# ESP32-Hutschiene-2_0.net
KiCad netlist of a schematic drawn in EAGLE
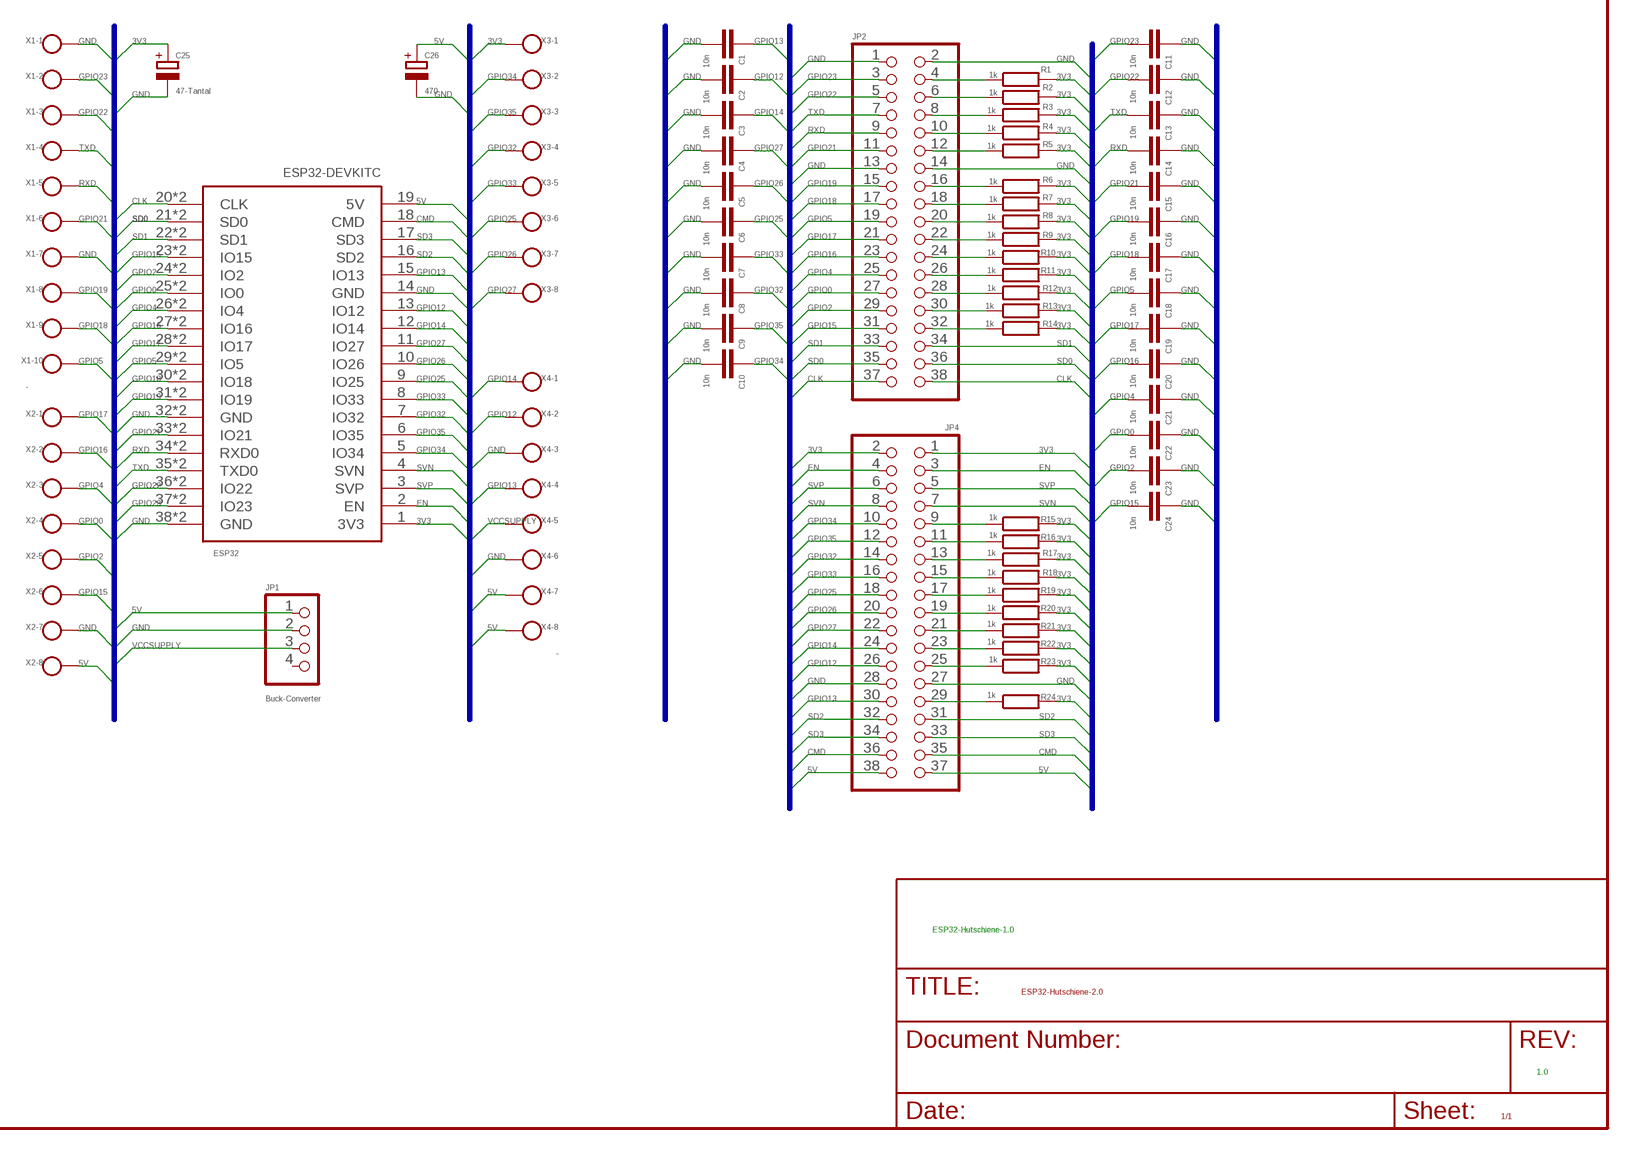
[diagram p0: schematic, sheet 1]

(export (version "E")
  (design (tool "Eeschema 10.0.6"))
  (components
    (comp (ref "C1")
      (value "10n")
      (footprint "eagle-import:C0603")
      (libsource (lib "eagle-import") (part "C-EUC0603"))
    )
    (comp (ref "C2")
      (value "10n")
      (footprint "eagle-import:C0603")
      (libsource (lib "eagle-import") (part "C-EUC0603"))
    )
    (comp (ref "C3")
      (value "10n")
      (footprint "eagle-import:C0603")
      (libsource (lib "eagle-import") (part "C-EUC0603"))
    )
    (comp (ref "C4")
      (value "10n")
      (footprint "eagle-import:C0603")
      (libsource (lib "eagle-import") (part "C-EUC0603"))
    )
    (comp (ref "C5")
      (value "10n")
      (footprint "eagle-import:C0603")
      (libsource (lib "eagle-import") (part "C-EUC0603"))
    )
    (comp (ref "C6")
      (value "10n")
      (footprint "eagle-import:C0603")
      (libsource (lib "eagle-import") (part "C-EUC0603"))
    )
    (comp (ref "C7")
      (value "10n")
      (footprint "eagle-import:C0603")
      (libsource (lib "eagle-import") (part "C-EUC0603"))
    )
    (comp (ref "C8")
      (value "10n")
      (footprint "eagle-import:C0603")
      (libsource (lib "eagle-import") (part "C-EUC0603"))
    )
    (comp (ref "C9")
      (value "10n")
      (footprint "eagle-import:C0603")
      (libsource (lib "eagle-import") (part "C-EUC0603"))
    )
    (comp (ref "C10")
      (value "10n")
      (footprint "eagle-import:C0603")
      (libsource (lib "eagle-import") (part "C-EUC0603"))
    )
    (comp (ref "C11")
      (value "10n")
      (footprint "eagle-import:C0603")
      (libsource (lib "eagle-import") (part "C-EUC0603"))
    )
    (comp (ref "C12")
      (value "10n")
      (footprint "eagle-import:C0603")
      (libsource (lib "eagle-import") (part "C-EUC0603"))
    )
    (comp (ref "C13")
      (value "10n")
      (footprint "eagle-import:C0603")
      (libsource (lib "eagle-import") (part "C-EUC0603"))
    )
    (comp (ref "C14")
      (value "10n")
      (footprint "eagle-import:C0603")
      (libsource (lib "eagle-import") (part "C-EUC0603"))
    )
    (comp (ref "C15")
      (value "10n")
      (footprint "eagle-import:C0603")
      (libsource (lib "eagle-import") (part "C-EUC0603"))
    )
    (comp (ref "C16")
      (value "10n")
      (footprint "eagle-import:C0603")
      (libsource (lib "eagle-import") (part "C-EUC0603"))
    )
    (comp (ref "C17")
      (value "10n")
      (footprint "eagle-import:C0603")
      (libsource (lib "eagle-import") (part "C-EUC0603"))
    )
    (comp (ref "C18")
      (value "10n")
      (footprint "eagle-import:C0603")
      (libsource (lib "eagle-import") (part "C-EUC0603"))
    )
    (comp (ref "C19")
      (value "10n")
      (footprint "eagle-import:C0603")
      (libsource (lib "eagle-import") (part "C-EUC0603"))
    )
    (comp (ref "C20")
      (value "10n")
      (footprint "eagle-import:C0603")
      (libsource (lib "eagle-import") (part "C-EUC0603"))
    )
    (comp (ref "C21")
      (value "10n")
      (footprint "eagle-import:C0603")
      (libsource (lib "eagle-import") (part "C-EUC0603"))
    )
    (comp (ref "C22")
      (value "10n")
      (footprint "eagle-import:C0603")
      (libsource (lib "eagle-import") (part "C-EUC0603"))
    )
    (comp (ref "C23")
      (value "10n")
      (footprint "eagle-import:C0603")
      (libsource (lib "eagle-import") (part "C-EUC0603"))
    )
    (comp (ref "C24")
      (value "10n")
      (footprint "eagle-import:C0603")
      (libsource (lib "eagle-import") (part "C-EUC0603"))
    )
    (comp (ref "C25")
      (value "47-Tantal")
      (footprint "eagle-import:E3,5-8")
      (libsource (lib "eagle-import") (part "CPOL-EUE3.5-8"))
    )
    (comp (ref "C26")
      (value "470")
      (footprint "eagle-import:E3,5-8")
      (libsource (lib "eagle-import") (part "CPOL-EUE3.5-8"))
    )
    (comp (ref "ESP32")
      (value "ESP32-DEVKITC-38P")
      (footprint "eagle-import:ESP32-DEVKITC-38P")
      (libsource (lib "eagle-import") (part "ESP32-DEVKITC-38P"))
    )
    (comp (ref "JP1")
      (value "Buck-Converter")
      (footprint "eagle-import:1X04")
      (libsource (lib "eagle-import") (part "PINHD-1X4"))
    )
    (comp (ref "JP2")
      (value "PINHD-2X19")
      (footprint "eagle-import:2X19")
      (libsource (lib "eagle-import") (part "PINHD-2X19"))
    )
    (comp (ref "JP4")
      (value "PINHD-2X19")
      (footprint "eagle-import:2X19")
      (libsource (lib "eagle-import") (part "PINHD-2X19"))
    )
    (comp (ref "R1")
      (value "1k")
      (footprint "eagle-import:R0603")
      (libsource (lib "eagle-import") (part "R-EU_R0603"))
    )
    (comp (ref "R2")
      (value "1k")
      (footprint "eagle-import:R0603")
      (libsource (lib "eagle-import") (part "R-EU_R0603"))
    )
    (comp (ref "R3")
      (value "1k")
      (footprint "eagle-import:R0603")
      (libsource (lib "eagle-import") (part "R-EU_R0603"))
    )
    (comp (ref "R4")
      (value "1k")
      (footprint "eagle-import:R0603")
      (libsource (lib "eagle-import") (part "R-EU_R0603"))
    )
    (comp (ref "R5")
      (value "1k")
      (footprint "eagle-import:R0603")
      (libsource (lib "eagle-import") (part "R-EU_R0603"))
    )
    (comp (ref "R6")
      (value "1k")
      (footprint "eagle-import:R0603")
      (libsource (lib "eagle-import") (part "R-EU_R0603"))
    )
    (comp (ref "R7")
      (value "1k")
      (footprint "eagle-import:R0603")
      (libsource (lib "eagle-import") (part "R-EU_R0603"))
    )
    (comp (ref "R8")
      (value "1k")
      (footprint "eagle-import:R0603")
      (libsource (lib "eagle-import") (part "R-EU_R0603"))
    )
    (comp (ref "R9")
      (value "1k")
      (footprint "eagle-import:R0603")
      (libsource (lib "eagle-import") (part "R-EU_R0603"))
    )
    (comp (ref "R10")
      (value "1k")
      (footprint "eagle-import:R0603")
      (libsource (lib "eagle-import") (part "R-EU_R0603"))
    )
    (comp (ref "R11")
      (value "1k")
      (footprint "eagle-import:R0603")
      (libsource (lib "eagle-import") (part "R-EU_R0603"))
    )
    (comp (ref "R12")
      (value "1k")
      (footprint "eagle-import:R0603")
      (libsource (lib "eagle-import") (part "R-EU_R0603"))
    )
    (comp (ref "R13")
      (value "1k")
      (footprint "eagle-import:R0603")
      (libsource (lib "eagle-import") (part "R-EU_R0603"))
    )
    (comp (ref "R14")
      (value "1k")
      (footprint "eagle-import:R0603")
      (libsource (lib "eagle-import") (part "R-EU_R0603"))
    )
    (comp (ref "R15")
      (value "1k")
      (footprint "eagle-import:R0603")
      (libsource (lib "eagle-import") (part "R-EU_R0603"))
    )
    (comp (ref "R16")
      (value "1k")
      (footprint "eagle-import:R0603")
      (libsource (lib "eagle-import") (part "R-EU_R0603"))
    )
    (comp (ref "R17")
      (value "1k")
      (footprint "eagle-import:R0603")
      (libsource (lib "eagle-import") (part "R-EU_R0603"))
    )
    (comp (ref "R18")
      (value "1k")
      (footprint "eagle-import:R0603")
      (libsource (lib "eagle-import") (part "R-EU_R0603"))
    )
    (comp (ref "R19")
      (value "1k")
      (footprint "eagle-import:R0603")
      (libsource (lib "eagle-import") (part "R-EU_R0603"))
    )
    (comp (ref "R20")
      (value "1k")
      (footprint "eagle-import:R0603")
      (libsource (lib "eagle-import") (part "R-EU_R0603"))
    )
    (comp (ref "R21")
      (value "1k")
      (footprint "eagle-import:R0603")
      (libsource (lib "eagle-import") (part "R-EU_R0603"))
    )
    (comp (ref "R22")
      (value "1k")
      (footprint "eagle-import:R0603")
      (libsource (lib "eagle-import") (part "R-EU_R0603"))
    )
    (comp (ref "R23")
      (value "1k")
      (footprint "eagle-import:R0603")
      (libsource (lib "eagle-import") (part "R-EU_R0603"))
    )
    (comp (ref "R24")
      (value "1k")
      (footprint "eagle-import:R0603")
      (libsource (lib "eagle-import") (part "R-EU_R0603"))
    )
    (comp (ref "X1")
      (value "-")
      (footprint "eagle-import:W237-10P")
      (libsource (lib "eagle-import") (part "W237-10P"))
    )
    (comp (ref "X2")
      (value "W237-08P")
      (footprint "eagle-import:W237-8P")
      (libsource (lib "eagle-import") (part "W237-08P"))
    )
    (comp (ref "X3")
      (value "W237-09P")
      (footprint "eagle-import:W237-9P")
      (libsource (lib "eagle-import") (part "W237-09P"))
    )
    (comp (ref "X4")
      (value "-")
      (footprint "eagle-import:W237-8P")
      (libsource (lib "eagle-import") (part "W237-08P"))
    )
  )
  (nets
    (net (code "1") (name "/3V3") (class "Default")
      (node (ref "C25") (pin "+") (pinfunction "+_+") (pintype "passive"))
      (node (ref "ESP32") (pin "1") (pinfunction "3V3_1") (pintype "bidirectional"))
      (node (ref "JP4") (pin "1") (pinfunction "1_1") (pintype "passive"))
      (node (ref "JP4") (pin "2") (pinfunction "2_2") (pintype "passive"))
      (node (ref "R1") (pin "2") (pinfunction "2_2") (pintype "passive"))
      (node (ref "R10") (pin "2") (pinfunction "2_2") (pintype "passive"))
      (node (ref "R11") (pin "2") (pinfunction "2_2") (pintype "passive"))
      (node (ref "R12") (pin "2") (pinfunction "2_2") (pintype "passive"))
      (node (ref "R13") (pin "2") (pinfunction "2_2") (pintype "passive"))
      (node (ref "R14") (pin "2") (pinfunction "2_2") (pintype "passive"))
      (node (ref "R15") (pin "2") (pinfunction "2_2") (pintype "passive"))
      (node (ref "R16") (pin "2") (pinfunction "2_2") (pintype "passive"))
      (node (ref "R17") (pin "2") (pinfunction "2_2") (pintype "passive"))
      (node (ref "R18") (pin "2") (pinfunction "2_2") (pintype "passive"))
      (node (ref "R19") (pin "2") (pinfunction "2_2") (pintype "passive"))
      (node (ref "R2") (pin "2") (pinfunction "2_2") (pintype "passive"))
      (node (ref "R20") (pin "2") (pinfunction "2_2") (pintype "passive"))
      (node (ref "R21") (pin "2") (pinfunction "2_2") (pintype "passive"))
      (node (ref "R22") (pin "2") (pinfunction "2_2") (pintype "passive"))
      (node (ref "R23") (pin "2") (pinfunction "2_2") (pintype "passive"))
      (node (ref "R24") (pin "2") (pinfunction "2_2") (pintype "passive"))
      (node (ref "R3") (pin "2") (pinfunction "2_2") (pintype "passive"))
      (node (ref "R4") (pin "2") (pinfunction "2_2") (pintype "passive"))
      (node (ref "R5") (pin "2") (pinfunction "2_2") (pintype "passive"))
      (node (ref "R6") (pin "2") (pinfunction "2_2") (pintype "passive"))
      (node (ref "R7") (pin "2") (pinfunction "2_2") (pintype "passive"))
      (node (ref "R8") (pin "2") (pinfunction "2_2") (pintype "passive"))
      (node (ref "R9") (pin "2") (pinfunction "2_2") (pintype "passive"))
      (node (ref "X3") (pin "1") (pinfunction "KL_1") (pintype "passive"))
    )
    (net (code "2") (name "/5V") (class "Default")
      (node (ref "C26") (pin "+") (pinfunction "+_+") (pintype "passive"))
      (node (ref "ESP32") (pin "19") (pinfunction "5V_19") (pintype "bidirectional"))
      (node (ref "JP1") (pin "1") (pinfunction "1_1") (pintype "passive"))
      (node (ref "JP4") (pin "37") (pinfunction "37_37") (pintype "passive"))
      (node (ref "JP4") (pin "38") (pinfunction "38_38") (pintype "passive"))
      (node (ref "X2") (pin "8") (pinfunction "KL_8") (pintype "passive"))
      (node (ref "X4") (pin "7") (pinfunction "KL_7") (pintype "passive"))
      (node (ref "X4") (pin "8") (pinfunction "KL_8") (pintype "passive"))
    )
    (net (code "3") (name "/CLK") (class "Default")
      (node (ref "ESP32") (pin "20") (pinfunction "CLK_20") (pintype "bidirectional"))
      (node (ref "ESP32") (pin "57") (pinfunction "CLK_57") (pintype "bidirectional"))
      (node (ref "JP2") (pin "37") (pinfunction "37_37") (pintype "passive"))
      (node (ref "JP2") (pin "38") (pinfunction "38_38") (pintype "passive"))
    )
    (net (code "4") (name "/CMD") (class "Default")
      (node (ref "ESP32") (pin "18") (pinfunction "CMD_18") (pintype "bidirectional"))
      (node (ref "JP4") (pin "35") (pinfunction "35_35") (pintype "passive"))
      (node (ref "JP4") (pin "36") (pinfunction "36_36") (pintype "passive"))
    )
    (net (code "5") (name "/EN") (class "Default")
      (node (ref "ESP32") (pin "2") (pinfunction "EN_2") (pintype "bidirectional"))
      (node (ref "JP4") (pin "3") (pinfunction "3_3") (pintype "passive"))
      (node (ref "JP4") (pin "4") (pinfunction "4_4") (pintype "passive"))
    )
    (net (code "6") (name "/GND") (class "Default")
      (node (ref "C1") (pin "2") (pinfunction "2_2") (pintype "passive"))
      (node (ref "C10") (pin "2") (pinfunction "2_2") (pintype "passive"))
      (node (ref "C11") (pin "1") (pinfunction "1_1") (pintype "passive"))
      (node (ref "C12") (pin "1") (pinfunction "1_1") (pintype "passive"))
      (node (ref "C13") (pin "1") (pinfunction "1_1") (pintype "passive"))
      (node (ref "C14") (pin "1") (pinfunction "1_1") (pintype "passive"))
      (node (ref "C15") (pin "1") (pinfunction "1_1") (pintype "passive"))
      (node (ref "C16") (pin "1") (pinfunction "1_1") (pintype "passive"))
      (node (ref "C17") (pin "1") (pinfunction "1_1") (pintype "passive"))
      (node (ref "C18") (pin "1") (pinfunction "1_1") (pintype "passive"))
      (node (ref "C19") (pin "1") (pinfunction "1_1") (pintype "passive"))
      (node (ref "C2") (pin "2") (pinfunction "2_2") (pintype "passive"))
      (node (ref "C20") (pin "1") (pinfunction "1_1") (pintype "passive"))
      (node (ref "C21") (pin "1") (pinfunction "1_1") (pintype "passive"))
      (node (ref "C22") (pin "1") (pinfunction "1_1") (pintype "passive"))
      (node (ref "C23") (pin "1") (pinfunction "1_1") (pintype "passive"))
      (node (ref "C24") (pin "1") (pinfunction "1_1") (pintype "passive"))
      (node (ref "C25") (pin "-") (pinfunction "-_-") (pintype "passive"))
      (node (ref "C26") (pin "-") (pinfunction "-_-") (pintype "passive"))
      (node (ref "C3") (pin "2") (pinfunction "2_2") (pintype "passive"))
      (node (ref "C4") (pin "2") (pinfunction "2_2") (pintype "passive"))
      (node (ref "C5") (pin "2") (pinfunction "2_2") (pintype "passive"))
      (node (ref "C6") (pin "2") (pinfunction "2_2") (pintype "passive"))
      (node (ref "C7") (pin "2") (pinfunction "2_2") (pintype "passive"))
      (node (ref "C8") (pin "2") (pinfunction "2_2") (pintype "passive"))
      (node (ref "C9") (pin "2") (pinfunction "2_2") (pintype "passive"))
      (node (ref "ESP32") (pin "14") (pinfunction "GND_14") (pintype "bidirectional"))
      (node (ref "ESP32") (pin "32") (pinfunction "GND_32") (pintype "bidirectional"))
      (node (ref "ESP32") (pin "38") (pinfunction "GND_38") (pintype "bidirectional"))
      (node (ref "ESP32") (pin "39") (pinfunction "GND_39") (pintype "bidirectional"))
      (node (ref "ESP32") (pin "45") (pinfunction "GND_45") (pintype "bidirectional"))
      (node (ref "JP1") (pin "2") (pinfunction "2_2") (pintype "passive"))
      (node (ref "JP2") (pin "1") (pinfunction "1_1") (pintype "passive"))
      (node (ref "JP2") (pin "13") (pinfunction "13_13") (pintype "passive"))
      (node (ref "JP2") (pin "14") (pinfunction "14_14") (pintype "passive"))
      (node (ref "JP2") (pin "2") (pinfunction "2_2") (pintype "passive"))
      (node (ref "JP4") (pin "27") (pinfunction "27_27") (pintype "passive"))
      (node (ref "JP4") (pin "28") (pinfunction "28_28") (pintype "passive"))
      (node (ref "X1") (pin "1") (pinfunction "KL_1") (pintype "passive"))
      (node (ref "X1") (pin "7") (pinfunction "KL_7") (pintype "passive"))
      (node (ref "X2") (pin "7") (pinfunction "KL_7") (pintype "passive"))
      (node (ref "X4") (pin "3") (pinfunction "KL_3") (pintype "passive"))
      (node (ref "X4") (pin "6") (pinfunction "KL_6") (pintype "passive"))
    )
    (net (code "7") (name "/GPIO0") (class "Default")
      (node (ref "C22") (pin "2") (pinfunction "2_2") (pintype "passive"))
      (node (ref "ESP32") (pin "25") (pinfunction "IO0_25") (pintype "bidirectional"))
      (node (ref "ESP32") (pin "52") (pinfunction "IO0_52") (pintype "bidirectional"))
      (node (ref "JP2") (pin "27") (pinfunction "27_27") (pintype "passive"))
      (node (ref "X2") (pin "4") (pinfunction "KL_4") (pintype "passive"))
    )
    (net (code "8") (name "/GPIO2") (class "Default")
      (node (ref "C23") (pin "2") (pinfunction "2_2") (pintype "passive"))
      (node (ref "ESP32") (pin "24") (pinfunction "IO2_24") (pintype "bidirectional"))
      (node (ref "ESP32") (pin "53") (pinfunction "IO2_53") (pintype "bidirectional"))
      (node (ref "JP2") (pin "29") (pinfunction "29_29") (pintype "passive"))
      (node (ref "X2") (pin "5") (pinfunction "KL_5") (pintype "passive"))
    )
    (net (code "9") (name "/GPIO4") (class "Default")
      (node (ref "C21") (pin "2") (pinfunction "2_2") (pintype "passive"))
      (node (ref "ESP32") (pin "26") (pinfunction "IO4_26") (pintype "bidirectional"))
      (node (ref "ESP32") (pin "51") (pinfunction "IO4_51") (pintype "bidirectional"))
      (node (ref "JP2") (pin "25") (pinfunction "25_25") (pintype "passive"))
      (node (ref "X2") (pin "3") (pinfunction "KL_3") (pintype "passive"))
    )
    (net (code "10") (name "/GPIO5") (class "Default")
      (node (ref "C18") (pin "2") (pinfunction "2_2") (pintype "passive"))
      (node (ref "ESP32") (pin "29") (pinfunction "IO5_29") (pintype "bidirectional"))
      (node (ref "ESP32") (pin "48") (pinfunction "IO5_48") (pintype "bidirectional"))
      (node (ref "JP2") (pin "19") (pinfunction "19_19") (pintype "passive"))
      (node (ref "X1") (pin "10") (pinfunction "KL_10") (pintype "passive"))
    )
    (net (code "11") (name "/GPIO12") (class "Default")
      (node (ref "C2") (pin "1") (pinfunction "1_1") (pintype "passive"))
      (node (ref "ESP32") (pin "13") (pinfunction "IO12_13") (pintype "bidirectional"))
      (node (ref "JP4") (pin "26") (pinfunction "26_26") (pintype "passive"))
      (node (ref "X4") (pin "2") (pinfunction "KL_2") (pintype "passive"))
    )
    (net (code "12") (name "/GPIO13") (class "Default")
      (node (ref "C1") (pin "1") (pinfunction "1_1") (pintype "passive"))
      (node (ref "ESP32") (pin "15") (pinfunction "IO13_15") (pintype "bidirectional"))
      (node (ref "JP4") (pin "30") (pinfunction "30_30") (pintype "passive"))
      (node (ref "X4") (pin "4") (pinfunction "KL_4") (pintype "passive"))
    )
    (net (code "13") (name "/GPIO14") (class "Default")
      (node (ref "C3") (pin "1") (pinfunction "1_1") (pintype "passive"))
      (node (ref "ESP32") (pin "12") (pinfunction "IO14_12") (pintype "bidirectional"))
      (node (ref "JP4") (pin "24") (pinfunction "24_24") (pintype "passive"))
      (node (ref "X4") (pin "1") (pinfunction "KL_1") (pintype "passive"))
    )
    (net (code "14") (name "/GPIO15") (class "Default")
      (node (ref "C24") (pin "2") (pinfunction "2_2") (pintype "passive"))
      (node (ref "ESP32") (pin "23") (pinfunction "IO15_23") (pintype "bidirectional"))
      (node (ref "ESP32") (pin "54") (pinfunction "IO15_54") (pintype "bidirectional"))
      (node (ref "JP2") (pin "31") (pinfunction "31_31") (pintype "passive"))
      (node (ref "X2") (pin "6") (pinfunction "KL_6") (pintype "passive"))
    )
    (net (code "15") (name "/GPIO16") (class "Default")
      (node (ref "C20") (pin "2") (pinfunction "2_2") (pintype "passive"))
      (node (ref "ESP32") (pin "27") (pinfunction "IO16_27") (pintype "bidirectional"))
      (node (ref "ESP32") (pin "50") (pinfunction "IO16_50") (pintype "bidirectional"))
      (node (ref "JP2") (pin "23") (pinfunction "23_23") (pintype "passive"))
      (node (ref "X2") (pin "2") (pinfunction "KL_2") (pintype "passive"))
    )
    (net (code "16") (name "/GPIO17") (class "Default")
      (node (ref "C19") (pin "2") (pinfunction "2_2") (pintype "passive"))
      (node (ref "ESP32") (pin "28") (pinfunction "IO17_28") (pintype "bidirectional"))
      (node (ref "ESP32") (pin "49") (pinfunction "IO17_49") (pintype "bidirectional"))
      (node (ref "JP2") (pin "21") (pinfunction "21_21") (pintype "passive"))
      (node (ref "X2") (pin "1") (pinfunction "KL_1") (pintype "passive"))
    )
    (net (code "17") (name "/GPIO18") (class "Default")
      (node (ref "C17") (pin "2") (pinfunction "2_2") (pintype "passive"))
      (node (ref "ESP32") (pin "30") (pinfunction "IO18_30") (pintype "bidirectional"))
      (node (ref "ESP32") (pin "47") (pinfunction "IO18_47") (pintype "bidirectional"))
      (node (ref "JP2") (pin "17") (pinfunction "17_17") (pintype "passive"))
      (node (ref "X1") (pin "9") (pinfunction "KL_9") (pintype "passive"))
    )
    (net (code "18") (name "/GPIO19") (class "Default")
      (node (ref "C16") (pin "2") (pinfunction "2_2") (pintype "passive"))
      (node (ref "ESP32") (pin "31") (pinfunction "IO19_31") (pintype "bidirectional"))
      (node (ref "ESP32") (pin "46") (pinfunction "IO19_46") (pintype "bidirectional"))
      (node (ref "JP2") (pin "15") (pinfunction "15_15") (pintype "passive"))
      (node (ref "X1") (pin "8") (pinfunction "KL_8") (pintype "passive"))
    )
    (net (code "19") (name "/GPIO21") (class "Default")
      (node (ref "C15") (pin "2") (pinfunction "2_2") (pintype "passive"))
      (node (ref "ESP32") (pin "33") (pinfunction "IO21_33") (pintype "bidirectional"))
      (node (ref "ESP32") (pin "44") (pinfunction "IO21_44") (pintype "bidirectional"))
      (node (ref "JP2") (pin "11") (pinfunction "11_11") (pintype "passive"))
      (node (ref "X1") (pin "6") (pinfunction "KL_6") (pintype "passive"))
    )
    (net (code "20") (name "/GPIO22") (class "Default")
      (node (ref "C12") (pin "2") (pinfunction "2_2") (pintype "passive"))
      (node (ref "ESP32") (pin "36") (pinfunction "IO22_36") (pintype "bidirectional"))
      (node (ref "ESP32") (pin "41") (pinfunction "IO22_41") (pintype "bidirectional"))
      (node (ref "JP2") (pin "5") (pinfunction "5_5") (pintype "passive"))
      (node (ref "X1") (pin "3") (pinfunction "KL_3") (pintype "passive"))
    )
    (net (code "21") (name "/GPIO23") (class "Default")
      (node (ref "C11") (pin "2") (pinfunction "2_2") (pintype "passive"))
      (node (ref "ESP32") (pin "37") (pinfunction "IO23_37") (pintype "bidirectional"))
      (node (ref "ESP32") (pin "40") (pinfunction "IO23_40") (pintype "bidirectional"))
      (node (ref "JP2") (pin "3") (pinfunction "3_3") (pintype "passive"))
      (node (ref "X1") (pin "2") (pinfunction "KL_2") (pintype "passive"))
    )
    (net (code "22") (name "/GPIO25") (class "Default")
      (node (ref "C6") (pin "1") (pinfunction "1_1") (pintype "passive"))
      (node (ref "ESP32") (pin "9") (pinfunction "IO25_9") (pintype "bidirectional"))
      (node (ref "JP4") (pin "18") (pinfunction "18_18") (pintype "passive"))
      (node (ref "X3") (pin "6") (pinfunction "KL_6") (pintype "passive"))
    )
    (net (code "23") (name "/GPIO26") (class "Default")
      (node (ref "C5") (pin "1") (pinfunction "1_1") (pintype "passive"))
      (node (ref "ESP32") (pin "10") (pinfunction "IO26_10") (pintype "bidirectional"))
      (node (ref "JP4") (pin "20") (pinfunction "20_20") (pintype "passive"))
      (node (ref "X3") (pin "7") (pinfunction "KL_7") (pintype "passive"))
    )
    (net (code "24") (name "/GPIO27") (class "Default")
      (node (ref "C4") (pin "1") (pinfunction "1_1") (pintype "passive"))
      (node (ref "ESP32") (pin "11") (pinfunction "IO27_11") (pintype "bidirectional"))
      (node (ref "JP4") (pin "22") (pinfunction "22_22") (pintype "passive"))
      (node (ref "X3") (pin "8") (pinfunction "KL_8") (pintype "passive"))
    )
    (net (code "25") (name "/GPIO32") (class "Default")
      (node (ref "C8") (pin "1") (pinfunction "1_1") (pintype "passive"))
      (node (ref "ESP32") (pin "7") (pinfunction "IO32_7") (pintype "bidirectional"))
      (node (ref "JP4") (pin "14") (pinfunction "14_14") (pintype "passive"))
      (node (ref "X3") (pin "4") (pinfunction "KL_4") (pintype "passive"))
    )
    (net (code "26") (name "/GPIO33") (class "Default")
      (node (ref "C7") (pin "1") (pinfunction "1_1") (pintype "passive"))
      (node (ref "ESP32") (pin "8") (pinfunction "IO33_8") (pintype "bidirectional"))
      (node (ref "JP4") (pin "16") (pinfunction "16_16") (pintype "passive"))
      (node (ref "X3") (pin "5") (pinfunction "KL_5") (pintype "passive"))
    )
    (net (code "27") (name "/GPIO34") (class "Default")
      (node (ref "C10") (pin "1") (pinfunction "1_1") (pintype "passive"))
      (node (ref "ESP32") (pin "5") (pinfunction "IO34_5") (pintype "bidirectional"))
      (node (ref "JP4") (pin "10") (pinfunction "10_10") (pintype "passive"))
      (node (ref "X3") (pin "2") (pinfunction "KL_2") (pintype "passive"))
    )
    (net (code "28") (name "/GPIO35") (class "Default")
      (node (ref "C9") (pin "1") (pinfunction "1_1") (pintype "passive"))
      (node (ref "ESP32") (pin "6") (pinfunction "IO35_6") (pintype "bidirectional"))
      (node (ref "JP4") (pin "12") (pinfunction "12_12") (pintype "passive"))
      (node (ref "X3") (pin "3") (pinfunction "KL_3") (pintype "passive"))
    )
    (net (code "29") (name "/RXD") (class "Default")
      (node (ref "C14") (pin "2") (pinfunction "2_2") (pintype "passive"))
      (node (ref "ESP32") (pin "34") (pinfunction "RXD0_34") (pintype "bidirectional"))
      (node (ref "ESP32") (pin "43") (pinfunction "RXD0_43") (pintype "bidirectional"))
      (node (ref "JP2") (pin "9") (pinfunction "9_9") (pintype "passive"))
      (node (ref "X1") (pin "5") (pinfunction "KL_5") (pintype "passive"))
    )
    (net (code "30") (name "/SD0") (class "Default")
      (node (ref "ESP32") (pin "21") (pinfunction "SD0_21") (pintype "bidirectional"))
      (node (ref "ESP32") (pin "56") (pinfunction "SD0_56") (pintype "bidirectional"))
      (node (ref "JP2") (pin "35") (pinfunction "35_35") (pintype "passive"))
      (node (ref "JP2") (pin "36") (pinfunction "36_36") (pintype "passive"))
    )
    (net (code "31") (name "/SD1") (class "Default")
      (node (ref "ESP32") (pin "22") (pinfunction "SD1_22") (pintype "bidirectional"))
      (node (ref "ESP32") (pin "55") (pinfunction "SD1_55") (pintype "bidirectional"))
      (node (ref "JP2") (pin "33") (pinfunction "33_33") (pintype "passive"))
      (node (ref "JP2") (pin "34") (pinfunction "34_34") (pintype "passive"))
    )
    (net (code "32") (name "/SD2") (class "Default")
      (node (ref "ESP32") (pin "16") (pinfunction "SD2_16") (pintype "bidirectional"))
      (node (ref "JP4") (pin "31") (pinfunction "31_31") (pintype "passive"))
      (node (ref "JP4") (pin "32") (pinfunction "32_32") (pintype "passive"))
    )
    (net (code "33") (name "/SD3") (class "Default")
      (node (ref "ESP32") (pin "17") (pinfunction "SD3_17") (pintype "bidirectional"))
      (node (ref "JP4") (pin "33") (pinfunction "33_33") (pintype "passive"))
      (node (ref "JP4") (pin "34") (pinfunction "34_34") (pintype "passive"))
    )
    (net (code "34") (name "/SVN") (class "Default")
      (node (ref "ESP32") (pin "4") (pinfunction "SVN_4") (pintype "bidirectional"))
      (node (ref "JP4") (pin "7") (pinfunction "7_7") (pintype "passive"))
      (node (ref "JP4") (pin "8") (pinfunction "8_8") (pintype "passive"))
    )
    (net (code "35") (name "/SVP") (class "Default")
      (node (ref "ESP32") (pin "3") (pinfunction "SVP_3") (pintype "bidirectional"))
      (node (ref "JP4") (pin "5") (pinfunction "5_5") (pintype "passive"))
      (node (ref "JP4") (pin "6") (pinfunction "6_6") (pintype "passive"))
    )
    (net (code "36") (name "/TXD") (class "Default")
      (node (ref "C13") (pin "2") (pinfunction "2_2") (pintype "passive"))
      (node (ref "ESP32") (pin "35") (pinfunction "TXD0_35") (pintype "bidirectional"))
      (node (ref "ESP32") (pin "42") (pinfunction "TXD0_42") (pintype "bidirectional"))
      (node (ref "JP2") (pin "7") (pinfunction "7_7") (pintype "passive"))
      (node (ref "X1") (pin "4") (pinfunction "KL_4") (pintype "passive"))
    )
    (net (code "37") (name "/VCCSUPPLY") (class "Default")
      (node (ref "JP1") (pin "3") (pinfunction "3_3") (pintype "passive"))
      (node (ref "X4") (pin "5") (pinfunction "KL_5") (pintype "passive"))
    )
    (net (code "39") (name "Net-(JP2-Pad4)") (class "Default")
      (node (ref "JP2") (pin "4") (pinfunction "4_4") (pintype "passive"))
      (node (ref "R1") (pin "1") (pinfunction "1_1") (pintype "passive"))
    )
    (net (code "40") (name "Net-(JP2-Pad6)") (class "Default")
      (node (ref "JP2") (pin "6") (pinfunction "6_6") (pintype "passive"))
      (node (ref "R2") (pin "1") (pinfunction "1_1") (pintype "passive"))
    )
    (net (code "41") (name "Net-(JP2-Pad8)") (class "Default")
      (node (ref "JP2") (pin "8") (pinfunction "8_8") (pintype "passive"))
      (node (ref "R3") (pin "1") (pinfunction "1_1") (pintype "passive"))
    )
    (net (code "42") (name "Net-(JP2-Pad10)") (class "Default")
      (node (ref "JP2") (pin "10") (pinfunction "10_10") (pintype "passive"))
      (node (ref "R4") (pin "1") (pinfunction "1_1") (pintype "passive"))
    )
    (net (code "43") (name "Net-(JP2-Pad12)") (class "Default")
      (node (ref "JP2") (pin "12") (pinfunction "12_12") (pintype "passive"))
      (node (ref "R5") (pin "1") (pinfunction "1_1") (pintype "passive"))
    )
    (net (code "44") (name "Net-(JP2-Pad16)") (class "Default")
      (node (ref "JP2") (pin "16") (pinfunction "16_16") (pintype "passive"))
      (node (ref "R6") (pin "1") (pinfunction "1_1") (pintype "passive"))
    )
    (net (code "45") (name "Net-(JP2-Pad18)") (class "Default")
      (node (ref "JP2") (pin "18") (pinfunction "18_18") (pintype "passive"))
      (node (ref "R7") (pin "1") (pinfunction "1_1") (pintype "passive"))
    )
    (net (code "46") (name "Net-(JP2-Pad20)") (class "Default")
      (node (ref "JP2") (pin "20") (pinfunction "20_20") (pintype "passive"))
      (node (ref "R8") (pin "1") (pinfunction "1_1") (pintype "passive"))
    )
    (net (code "47") (name "Net-(JP2-Pad22)") (class "Default")
      (node (ref "JP2") (pin "22") (pinfunction "22_22") (pintype "passive"))
      (node (ref "R9") (pin "1") (pinfunction "1_1") (pintype "passive"))
    )
    (net (code "48") (name "Net-(JP2-Pad24)") (class "Default")
      (node (ref "JP2") (pin "24") (pinfunction "24_24") (pintype "passive"))
      (node (ref "R10") (pin "1") (pinfunction "1_1") (pintype "passive"))
    )
    (net (code "49") (name "Net-(JP2-Pad26)") (class "Default")
      (node (ref "JP2") (pin "26") (pinfunction "26_26") (pintype "passive"))
      (node (ref "R11") (pin "1") (pinfunction "1_1") (pintype "passive"))
    )
    (net (code "50") (name "Net-(JP2-Pad28)") (class "Default")
      (node (ref "JP2") (pin "28") (pinfunction "28_28") (pintype "passive"))
      (node (ref "R12") (pin "1") (pinfunction "1_1") (pintype "passive"))
    )
    (net (code "51") (name "Net-(JP2-Pad30)") (class "Default")
      (node (ref "JP2") (pin "30") (pinfunction "30_30") (pintype "passive"))
      (node (ref "R13") (pin "1") (pinfunction "1_1") (pintype "passive"))
    )
    (net (code "52") (name "Net-(JP2-Pad32)") (class "Default")
      (node (ref "JP2") (pin "32") (pinfunction "32_32") (pintype "passive"))
      (node (ref "R14") (pin "1") (pinfunction "1_1") (pintype "passive"))
    )
    (net (code "53") (name "Net-(JP4-Pad9)") (class "Default")
      (node (ref "JP4") (pin "9") (pinfunction "9_9") (pintype "passive"))
      (node (ref "R15") (pin "1") (pinfunction "1_1") (pintype "passive"))
    )
    (net (code "54") (name "Net-(JP4-Pad11)") (class "Default")
      (node (ref "JP4") (pin "11") (pinfunction "11_11") (pintype "passive"))
      (node (ref "R16") (pin "1") (pinfunction "1_1") (pintype "passive"))
    )
    (net (code "55") (name "Net-(JP4-Pad13)") (class "Default")
      (node (ref "JP4") (pin "13") (pinfunction "13_13") (pintype "passive"))
      (node (ref "R17") (pin "1") (pinfunction "1_1") (pintype "passive"))
    )
    (net (code "56") (name "Net-(JP4-Pad15)") (class "Default")
      (node (ref "JP4") (pin "15") (pinfunction "15_15") (pintype "passive"))
      (node (ref "R18") (pin "1") (pinfunction "1_1") (pintype "passive"))
    )
    (net (code "57") (name "Net-(JP4-Pad17)") (class "Default")
      (node (ref "JP4") (pin "17") (pinfunction "17_17") (pintype "passive"))
      (node (ref "R19") (pin "1") (pinfunction "1_1") (pintype "passive"))
    )
    (net (code "58") (name "Net-(JP4-Pad19)") (class "Default")
      (node (ref "JP4") (pin "19") (pinfunction "19_19") (pintype "passive"))
      (node (ref "R20") (pin "1") (pinfunction "1_1") (pintype "passive"))
    )
    (net (code "59") (name "Net-(JP4-Pad21)") (class "Default")
      (node (ref "JP4") (pin "21") (pinfunction "21_21") (pintype "passive"))
      (node (ref "R21") (pin "1") (pinfunction "1_1") (pintype "passive"))
    )
    (net (code "60") (name "Net-(JP4-Pad23)") (class "Default")
      (node (ref "JP4") (pin "23") (pinfunction "23_23") (pintype "passive"))
      (node (ref "R22") (pin "1") (pinfunction "1_1") (pintype "passive"))
    )
    (net (code "61") (name "Net-(JP4-Pad25)") (class "Default")
      (node (ref "JP4") (pin "25") (pinfunction "25_25") (pintype "passive"))
      (node (ref "R23") (pin "1") (pinfunction "1_1") (pintype "passive"))
    )
    (net (code "62") (name "Net-(JP4-Pad29)") (class "Default")
      (node (ref "JP4") (pin "29") (pinfunction "29_29") (pintype "passive"))
      (node (ref "R24") (pin "1") (pinfunction "1_1") (pintype "passive"))
    )
    (net (code "63") (name "unconnected-(JP1-Pad4)") (class "Default")
      (node (ref "JP1") (pin "4") (pinfunction "4_4") (pintype "passive"))
    )
  )
)
